# SCH___2022-11-10.net
KiCad netlist of a schematic drawn in EasyEDA
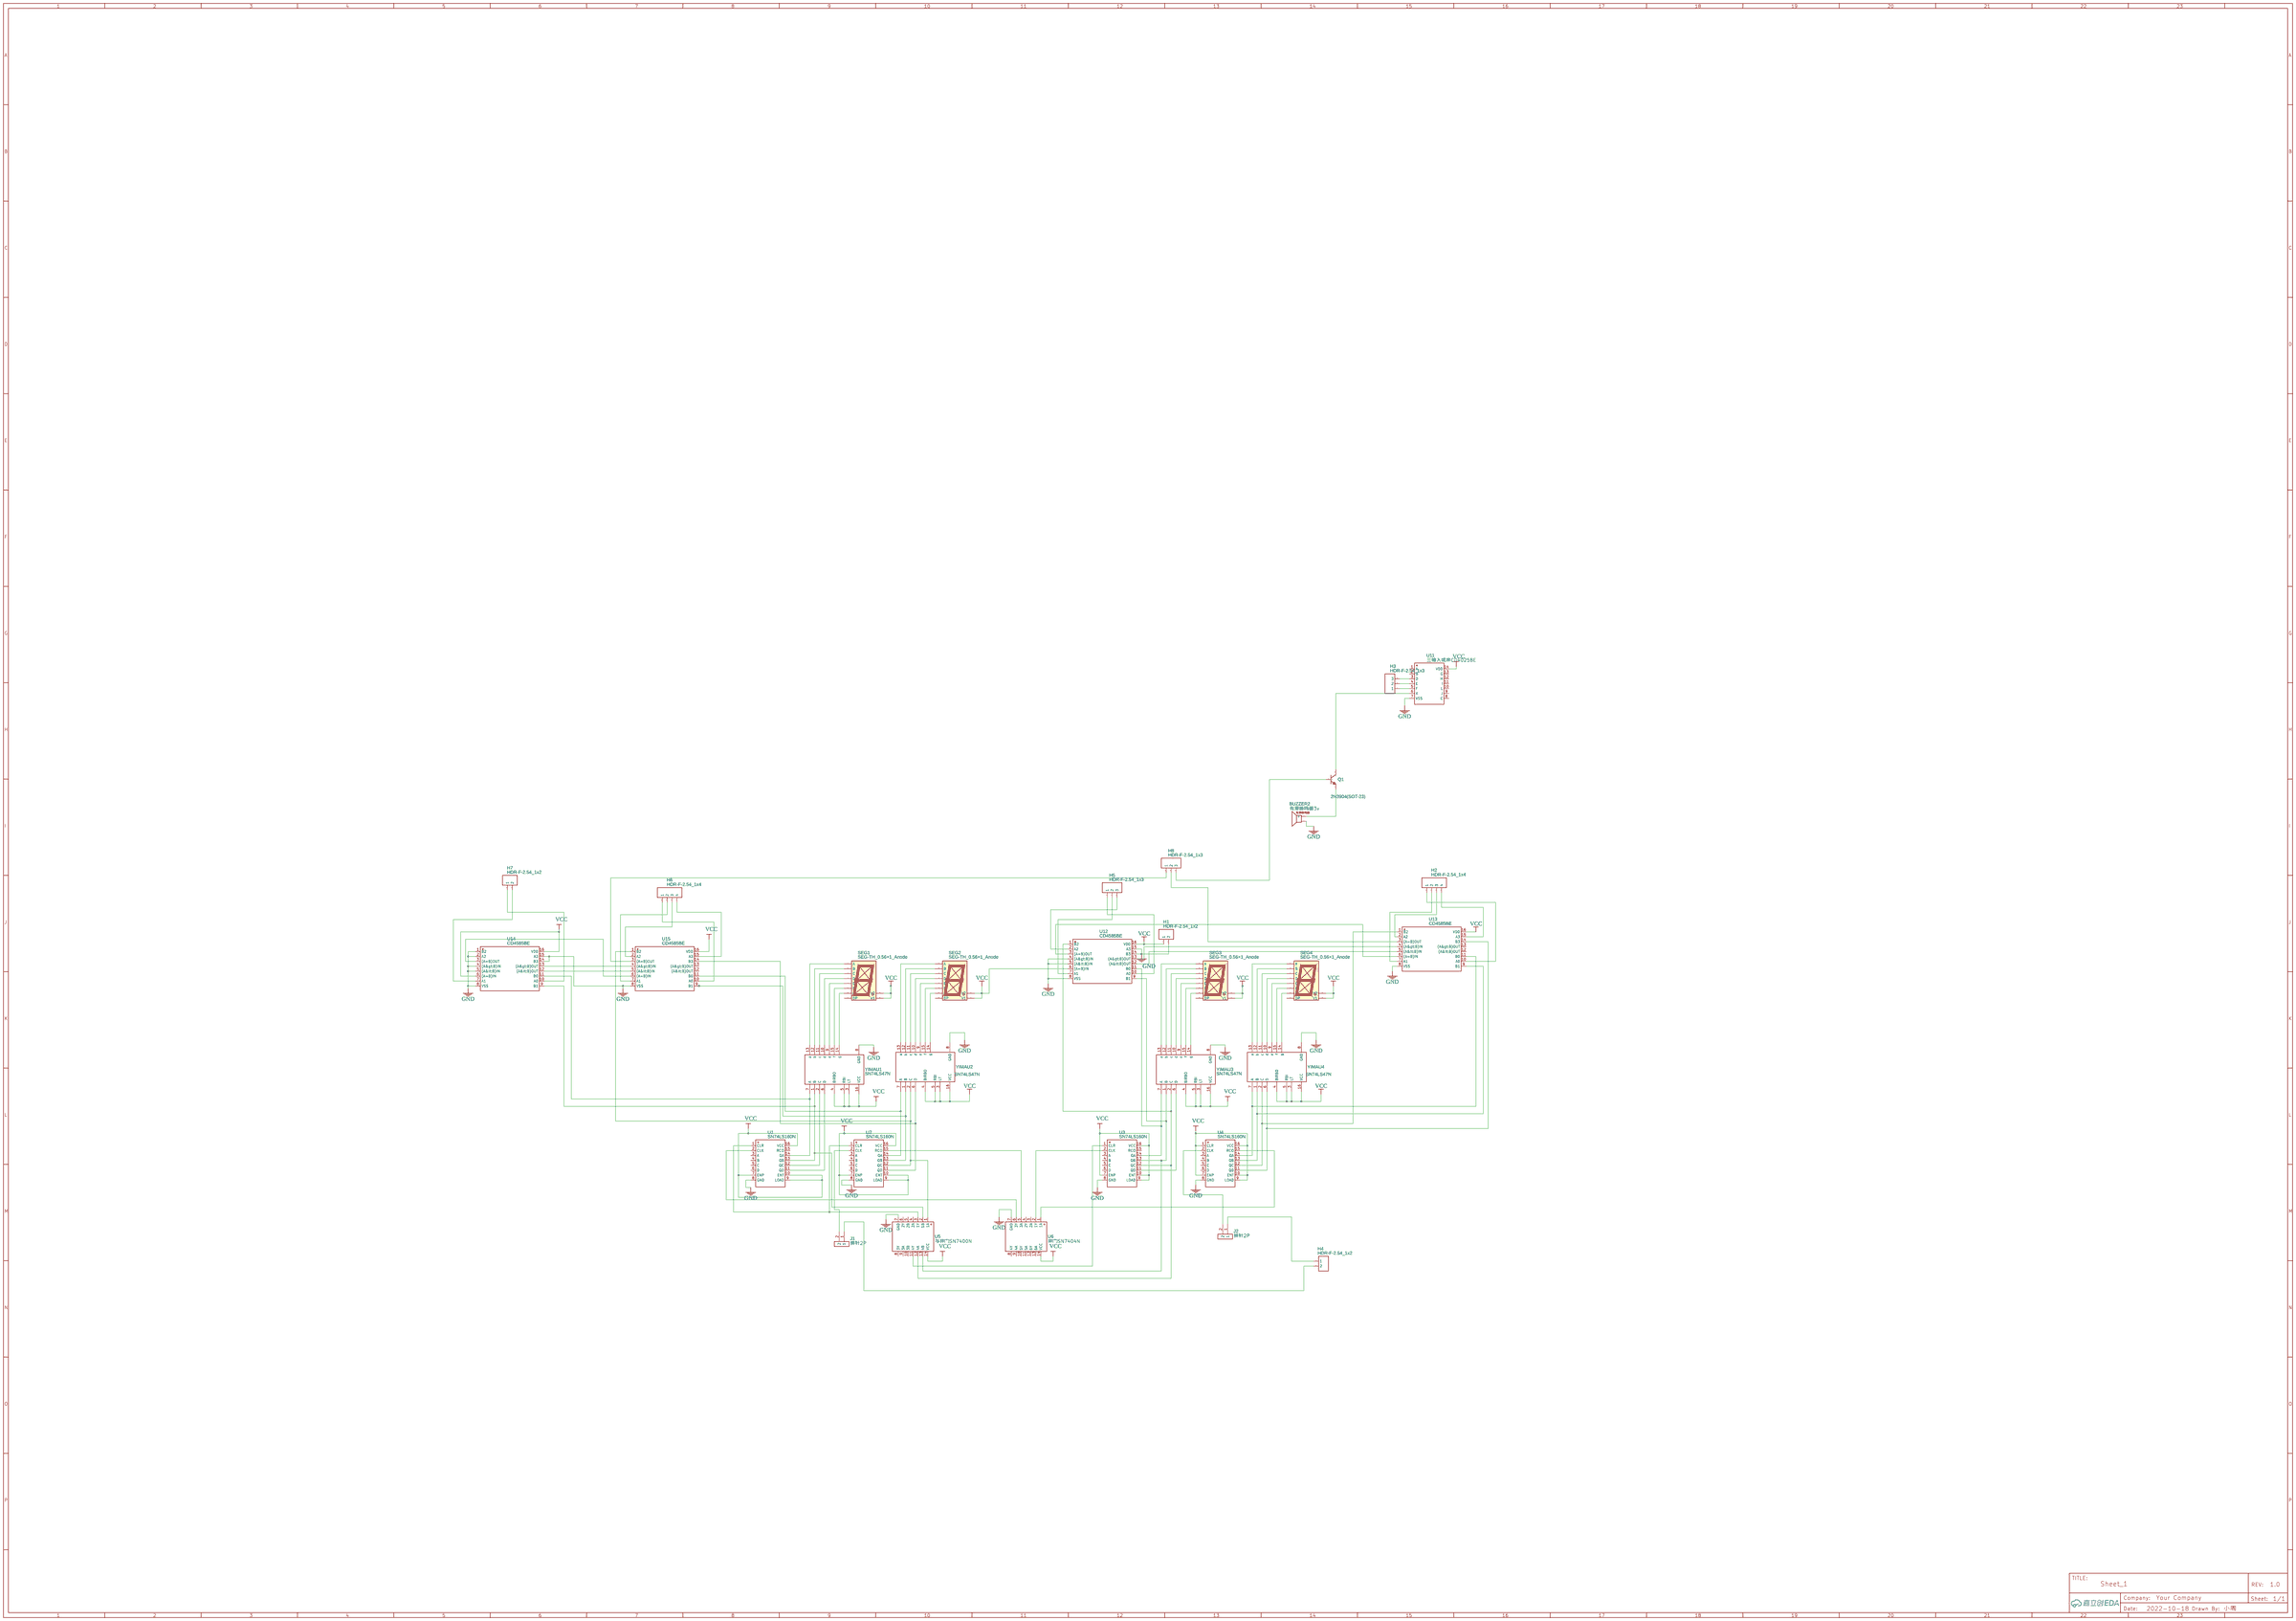
[diagram p0: schematic sheet]

(export (version "E")
  (design (tool "Eeschema 10.0.6"))
  (components
    (comp (ref "BUZZER2")
      (value "有源蜂鸣器3v")
      (fields (field (name "BOM_Manufacturer Part") "TMB12A12") (field (name "BOM_Supplier Part") "C96079"))
      (libsource (lib "") (part "有源蜂鸣器3v"))
    )
    (comp (ref "H1")
      (value "HDR-F-2.54_1x2")
      (fields (field (name "BOM_Supplier Part") "C49661"))
      (libsource (lib "") (part "HDR-F-2.54_1x2_1"))
    )
    (comp (ref "H2")
      (value "HDR-F-2.54_1x4")
      (fields (field (name "BOM_Supplier Part") "C225501"))
      (libsource (lib "") (part "HDR-F-2.54_1x4"))
    )
    (comp (ref "H3")
      (value "HDR-F-2.54_1x3")
      (fields (field (name "BOM_Supplier Part") "C146690"))
      (libsource (lib "") (part "HDR-F-2.54_1x3_1"))
    )
    (comp (ref "H4")
      (value "HDR-F-2.54_1x2")
      (fields (field (name "BOM_Supplier Part") "C49661"))
      (libsource (lib "") (part "HDR-F-2.54_1x2"))
    )
    (comp (ref "H5")
      (value "HDR-F-2.54_1x3")
      (fields (field (name "BOM_Supplier Part") "C146690"))
      (libsource (lib "") (part "HDR-F-2.54_1x3"))
    )
    (comp (ref "H6")
      (value "HDR-F-2.54_1x4")
      (fields (field (name "BOM_Supplier Part") "C225501"))
      (libsource (lib "") (part "HDR-F-2.54_1x4"))
    )
    (comp (ref "H7")
      (value "HDR-F-2.54_1x2")
      (fields (field (name "BOM_Supplier Part") "C49661"))
      (libsource (lib "") (part "HDR-F-2.54_1x2_1"))
    )
    (comp (ref "H8")
      (value "HDR-F-2.54_1x3")
      (fields (field (name "BOM_Supplier Part") "C146690"))
      (libsource (lib "") (part "HDR-F-2.54_1x3"))
    )
    (comp (ref "J1") (value "排针2P") (libsource (lib "") (part "排针2P")))
    (comp (ref "J2") (value "排针2P") (libsource (lib "") (part "排针2P")))
    (comp (ref "Q1")
      (value "2N3904(SOT-23)")
      (fields
        (field (name "BOM_Manufacturer Part") "2n3904S-RTK/PS")
        (field (name "BOM_Supplier Part") "C18536")
      )
      (libsource (lib "") (part "2N3904(SOT-23)"))
    )
    (comp (ref "SEG1")
      (value "SEG-TH_0.56×1_Anode")
      (fields (field (name "BOM_Supplier Part") "C8092"))
      (libsource (lib "") (part "SEG-TH_0.56×1_Anode"))
    )
    (comp (ref "SEG2")
      (value "SEG-TH_0.56×1_Anode")
      (fields (field (name "BOM_Supplier Part") "C8092"))
      (libsource (lib "") (part "SEG-TH_0.56×1_Anode"))
    )
    (comp (ref "SEG3")
      (value "SEG-TH_0.56×1_Anode")
      (fields (field (name "BOM_Supplier Part") "C8092"))
      (libsource (lib "") (part "SEG-TH_0.56×1_Anode"))
    )
    (comp (ref "SEG4")
      (value "SEG-TH_0.56×1_Anode")
      (fields (field (name "BOM_Supplier Part") "C8092"))
      (libsource (lib "") (part "SEG-TH_0.56×1_Anode"))
    )
    (comp (ref "U1")
      (value "SN74LS160N")
      (fields
        (field (name "BOM_Manufacturer Part") "CC0805JRNPO9BN821")
        (field (name "BOM_Supplier Part") "C113834")
      )
      (libsource (lib "") (part "SN74LS160N"))
    )
    (comp (ref "U2")
      (value "SN74LS160N")
      (fields
        (field (name "BOM_Manufacturer Part") "CC0805JRNPO9BN821")
        (field (name "BOM_Supplier Part") "C113834")
      )
      (libsource (lib "") (part "SN74LS160N"))
    )
    (comp (ref "U3")
      (value "SN74LS160N")
      (fields
        (field (name "BOM_Manufacturer Part") "CC0805JRNPO9BN821")
        (field (name "BOM_Supplier Part") "C113834")
      )
      (libsource (lib "") (part "SN74LS160N"))
    )
    (comp (ref "U4")
      (value "SN74LS160N")
      (fields
        (field (name "BOM_Manufacturer Part") "CC0805JRNPO9BN821")
        (field (name "BOM_Supplier Part") "C113834")
      )
      (libsource (lib "") (part "SN74LS160N"))
    )
    (comp (ref "U5") (value "与非门SN7400N") (libsource (lib "") (part "SN7400N")))
    (comp (ref "U6") (value "非门SN7404N") (libsource (lib "") (part "SN7404N")))
    (comp (ref "U11")
      (value "三输入或非CD4025BE")
      (fields (field (name "BOM_Manufacturer Part") "CD4025BE") (field (name "BOM_Supplier Part") "C28214"))
      (libsource (lib "") (part "CD4025BE"))
    )
    (comp (ref "U12")
      (value "CD4585BE")
      (fields (field (name "BOM_Supplier Part") "C31466"))
      (libsource (lib "") (part "CD4585BE"))
    )
    (comp (ref "U13")
      (value "CD4585BE")
      (fields (field (name "BOM_Supplier Part") "C31466"))
      (libsource (lib "") (part "CD4585BE"))
    )
    (comp (ref "U14")
      (value "CD4585BE")
      (fields (field (name "BOM_Supplier Part") "C31466"))
      (libsource (lib "") (part "CD4585BE"))
    )
    (comp (ref "U15")
      (value "CD4585BE")
      (fields (field (name "BOM_Supplier Part") "C31466"))
      (libsource (lib "") (part "CD4585BE"))
    )
    (comp (ref "YIMAU1")
      (value "SN74LS47N")
      (fields (field (name "BOM_Supplier Part") "C129379"))
      (libsource (lib "") (part "Unknown_1690_-1115"))
    )
    (comp (ref "YIMAU2")
      (value "SN74LS47N")
      (fields (field (name "BOM_Supplier Part") "C129379"))
      (libsource (lib "") (part "Unknown_1875_-1120"))
    )
    (comp (ref "YIMAU3")
      (value "SN74LS47N")
      (fields (field (name "BOM_Supplier Part") "C129379"))
      (libsource (lib "") (part "Unknown_2405_-1115"))
    )
    (comp (ref "YIMAU4")
      (value "SN74LS47N")
      (fields (field (name "BOM_Supplier Part") "C129379"))
      (libsource (lib "") (part "Unknown_2590_-1120"))
    )
  )
  (nets
    (net (code "1") (name "GND") (class "Default")
      (node (ref "BUZZER2") (pin "-") (pinfunction "-_-") (pintype "unspecified"))
      (node (ref "H1") (pin "2") (pinfunction "2_2") (pintype "input"))
      (node (ref "U1") (pin "8") (pinfunction "GND_8") (pintype "unspecified"))
      (node (ref "U11") (pin "7") (pinfunction "VSS_7") (pintype "unspecified"))
      (node (ref "U12") (pin "14") (pinfunction "B3_14") (pintype "unspecified"))
      (node (ref "U12") (pin "15") (pinfunction "A3_15") (pintype "unspecified"))
      (node (ref "U12") (pin "4") (pinfunction "(A&gt;B)IN_4") (pintype "unspecified"))
      (node (ref "U12") (pin "5") (pinfunction "(A&lt;B)IN_5") (pintype "unspecified"))
      (node (ref "U12") (pin "8") (pinfunction "VSS_8") (pintype "unspecified"))
      (node (ref "U13") (pin "8") (pinfunction "VSS_8") (pintype "unspecified"))
      (node (ref "U14") (pin "1") (pinfunction "B2_1") (pintype "unspecified"))
      (node (ref "U14") (pin "14") (pinfunction "B3_14") (pintype "unspecified"))
      (node (ref "U14") (pin "15") (pinfunction "A3_15") (pintype "unspecified"))
      (node (ref "U14") (pin "2") (pinfunction "A2_2") (pintype "unspecified"))
      (node (ref "U14") (pin "4") (pinfunction "(A&gt;B)IN_4") (pintype "unspecified"))
      (node (ref "U14") (pin "5") (pinfunction "(A&lt;B)IN_5") (pintype "unspecified"))
      (node (ref "U14") (pin "8") (pinfunction "VSS_8") (pintype "unspecified"))
      (node (ref "U15") (pin "8") (pinfunction "VSS_8") (pintype "unspecified"))
      (node (ref "U2") (pin "8") (pinfunction "GND_8") (pintype "unspecified"))
      (node (ref "U3") (pin "8") (pinfunction "GND_8") (pintype "unspecified"))
      (node (ref "U4") (pin "8") (pinfunction "GND_8") (pintype "unspecified"))
      (node (ref "U5") (pin "7") (pinfunction "GND_7") (pintype "unspecified"))
      (node (ref "U6") (pin "7") (pinfunction "GND_7") (pintype "unspecified"))
      (node (ref "YIMAU1") (pin "8") (pinfunction "GND_8") (pintype "passive"))
      (node (ref "YIMAU2") (pin "8") (pinfunction "GND_8") (pintype "passive"))
      (node (ref "YIMAU3") (pin "8") (pinfunction "GND_8") (pintype "passive"))
      (node (ref "YIMAU4") (pin "8") (pinfunction "GND_8") (pintype "passive"))
    )
    (net (code "2") (name "Net-(H4-Pad1)") (class "Default")
      (node (ref "H4") (pin "1") (pinfunction "1_1") (pintype "input"))
      (node (ref "J2") (pin "1") (pinfunction "1_1") (pintype "unspecified"))
    )
    (net (code "3") (name "Net-(H4-Pad2)") (class "Default")
      (node (ref "H4") (pin "2") (pinfunction "2_2") (pintype "input"))
      (node (ref "J1") (pin "1") (pinfunction "1_1") (pintype "unspecified"))
    )
    (net (code "4") (name "Net-(Q1-B)") (class "Default")
      (node (ref "H8") (pin "3") (pinfunction "3_3") (pintype "input"))
      (node (ref "Q1") (pin "2") (pinfunction "B_2") (pintype "input"))
    )
    (net (code "5") (name "Net-(Q1-C)") (class "Default")
      (node (ref "Q1") (pin "3") (pinfunction "C_3") (pintype "input"))
      (node (ref "U11") (pin "6") (pinfunction "K_6") (pintype "unspecified"))
    )
    (net (code "6") (name "Net-(Q1-E)") (class "Default")
      (node (ref "BUZZER2") (pin "+") (pinfunction "+_+") (pintype "unspecified"))
      (node (ref "Q1") (pin "1") (pinfunction "E_1") (pintype "input"))
    )
    (net (code "7") (name "Net-(SEG1-A)") (class "Default")
      (node (ref "SEG1") (pin "7") (pinfunction "A_7") (pintype "unspecified"))
      (node (ref "YIMAU1") (pin "13") (pinfunction "a_13") (pintype "unspecified"))
    )
    (net (code "8") (name "Net-(SEG1-B)") (class "Default")
      (node (ref "SEG1") (pin "6") (pinfunction "B_6") (pintype "unspecified"))
      (node (ref "YIMAU1") (pin "12") (pinfunction "b_12") (pintype "unspecified"))
    )
    (net (code "9") (name "Net-(SEG1-C)") (class "Default")
      (node (ref "SEG1") (pin "4") (pinfunction "C_4") (pintype "unspecified"))
      (node (ref "YIMAU1") (pin "11") (pinfunction "c_11") (pintype "unspecified"))
    )
    (net (code "10") (name "Net-(SEG1-D)") (class "Default")
      (node (ref "SEG1") (pin "2") (pinfunction "D_2") (pintype "unspecified"))
      (node (ref "YIMAU1") (pin "10") (pinfunction "d_10") (pintype "unspecified"))
    )
    (net (code "11") (name "Net-(SEG1-E)") (class "Default")
      (node (ref "SEG1") (pin "1") (pinfunction "E_1") (pintype "unspecified"))
      (node (ref "YIMAU1") (pin "9") (pinfunction "e_9") (pintype "unspecified"))
    )
    (net (code "12") (name "Net-(SEG1-F)") (class "Default")
      (node (ref "SEG1") (pin "9") (pinfunction "F_9") (pintype "unspecified"))
      (node (ref "YIMAU1") (pin "15") (pinfunction "f_15") (pintype "unspecified"))
    )
    (net (code "13") (name "Net-(SEG1-G)") (class "Default")
      (node (ref "SEG1") (pin "10") (pinfunction "G_10") (pintype "unspecified"))
      (node (ref "YIMAU1") (pin "14") (pinfunction "g_14") (pintype "unspecified"))
    )
    (net (code "14") (name "Net-(SEG2-A)") (class "Default")
      (node (ref "SEG2") (pin "7") (pinfunction "A_7") (pintype "unspecified"))
      (node (ref "YIMAU2") (pin "13") (pinfunction "a_13") (pintype "unspecified"))
    )
    (net (code "15") (name "Net-(SEG2-B)") (class "Default")
      (node (ref "SEG2") (pin "6") (pinfunction "B_6") (pintype "unspecified"))
      (node (ref "YIMAU2") (pin "12") (pinfunction "b_12") (pintype "unspecified"))
    )
    (net (code "16") (name "Net-(SEG2-C)") (class "Default")
      (node (ref "SEG2") (pin "4") (pinfunction "C_4") (pintype "unspecified"))
      (node (ref "YIMAU2") (pin "11") (pinfunction "c_11") (pintype "unspecified"))
    )
    (net (code "17") (name "Net-(SEG2-D)") (class "Default")
      (node (ref "SEG2") (pin "2") (pinfunction "D_2") (pintype "unspecified"))
      (node (ref "YIMAU2") (pin "10") (pinfunction "d_10") (pintype "unspecified"))
    )
    (net (code "18") (name "Net-(SEG2-E)") (class "Default")
      (node (ref "SEG2") (pin "1") (pinfunction "E_1") (pintype "unspecified"))
      (node (ref "YIMAU2") (pin "9") (pinfunction "e_9") (pintype "unspecified"))
    )
    (net (code "19") (name "Net-(SEG2-F)") (class "Default")
      (node (ref "SEG2") (pin "9") (pinfunction "F_9") (pintype "unspecified"))
      (node (ref "YIMAU2") (pin "15") (pinfunction "f_15") (pintype "unspecified"))
    )
    (net (code "20") (name "Net-(SEG2-G)") (class "Default")
      (node (ref "SEG2") (pin "10") (pinfunction "G_10") (pintype "unspecified"))
      (node (ref "YIMAU2") (pin "14") (pinfunction "g_14") (pintype "unspecified"))
    )
    (net (code "21") (name "Net-(SEG3-A)") (class "Default")
      (node (ref "SEG3") (pin "7") (pinfunction "A_7") (pintype "unspecified"))
      (node (ref "YIMAU3") (pin "13") (pinfunction "a_13") (pintype "unspecified"))
    )
    (net (code "22") (name "Net-(SEG3-B)") (class "Default")
      (node (ref "SEG3") (pin "6") (pinfunction "B_6") (pintype "unspecified"))
      (node (ref "YIMAU3") (pin "12") (pinfunction "b_12") (pintype "unspecified"))
    )
    (net (code "23") (name "Net-(SEG3-C)") (class "Default")
      (node (ref "SEG3") (pin "4") (pinfunction "C_4") (pintype "unspecified"))
      (node (ref "YIMAU3") (pin "11") (pinfunction "c_11") (pintype "unspecified"))
    )
    (net (code "24") (name "Net-(SEG3-D)") (class "Default")
      (node (ref "SEG3") (pin "2") (pinfunction "D_2") (pintype "unspecified"))
      (node (ref "YIMAU3") (pin "10") (pinfunction "d_10") (pintype "unspecified"))
    )
    (net (code "25") (name "Net-(SEG3-E)") (class "Default")
      (node (ref "SEG3") (pin "1") (pinfunction "E_1") (pintype "unspecified"))
      (node (ref "YIMAU3") (pin "9") (pinfunction "e_9") (pintype "unspecified"))
    )
    (net (code "26") (name "Net-(SEG3-F)") (class "Default")
      (node (ref "SEG3") (pin "9") (pinfunction "F_9") (pintype "unspecified"))
      (node (ref "YIMAU3") (pin "15") (pinfunction "f_15") (pintype "unspecified"))
    )
    (net (code "27") (name "Net-(SEG3-G)") (class "Default")
      (node (ref "SEG3") (pin "10") (pinfunction "G_10") (pintype "unspecified"))
      (node (ref "YIMAU3") (pin "14") (pinfunction "g_14") (pintype "unspecified"))
    )
    (net (code "28") (name "Net-(SEG4-A)") (class "Default")
      (node (ref "SEG4") (pin "7") (pinfunction "A_7") (pintype "unspecified"))
      (node (ref "YIMAU4") (pin "13") (pinfunction "a_13") (pintype "unspecified"))
    )
    (net (code "29") (name "Net-(SEG4-B)") (class "Default")
      (node (ref "SEG4") (pin "6") (pinfunction "B_6") (pintype "unspecified"))
      (node (ref "YIMAU4") (pin "12") (pinfunction "b_12") (pintype "unspecified"))
    )
    (net (code "30") (name "Net-(SEG4-C)") (class "Default")
      (node (ref "SEG4") (pin "4") (pinfunction "C_4") (pintype "unspecified"))
      (node (ref "YIMAU4") (pin "11") (pinfunction "c_11") (pintype "unspecified"))
    )
    (net (code "31") (name "Net-(SEG4-D)") (class "Default")
      (node (ref "SEG4") (pin "2") (pinfunction "D_2") (pintype "unspecified"))
      (node (ref "YIMAU4") (pin "10") (pinfunction "d_10") (pintype "unspecified"))
    )
    (net (code "32") (name "Net-(SEG4-E)") (class "Default")
      (node (ref "SEG4") (pin "1") (pinfunction "E_1") (pintype "unspecified"))
      (node (ref "YIMAU4") (pin "9") (pinfunction "e_9") (pintype "unspecified"))
    )
    (net (code "33") (name "Net-(SEG4-F)") (class "Default")
      (node (ref "SEG4") (pin "9") (pinfunction "F_9") (pintype "unspecified"))
      (node (ref "YIMAU4") (pin "15") (pinfunction "f_15") (pintype "unspecified"))
    )
    (net (code "34") (name "Net-(SEG4-G)") (class "Default")
      (node (ref "SEG4") (pin "10") (pinfunction "G_10") (pintype "unspecified"))
      (node (ref "YIMAU4") (pin "14") (pinfunction "g_14") (pintype "unspecified"))
    )
    (net (code "35") (name "Net-(U1-CLK)") (class "Default")
      (node (ref "U1") (pin "2") (pinfunction "CLK_2") (pintype "unspecified"))
      (node (ref "U6") (pin "6") (pinfunction "3Y_6") (pintype "unspecified"))
    )
    (net (code "36") (name "Net-(U1-CLR)") (class "Default")
      (node (ref "U1") (pin "1") (pinfunction "CLR_1") (pintype "unspecified"))
      (node (ref "U2") (pin "1") (pinfunction "CLR_1") (pintype "unspecified"))
      (node (ref "U5") (pin "3") (pinfunction "1Y_3") (pintype "unspecified"))
    )
    (net (code "37") (name "Net-(U1-QA)") (class "Default")
      (node (ref "U1") (pin "14") (pinfunction "QA_14") (pintype "unspecified"))
      (node (ref "U14") (pin "11") (pinfunction "B0_11") (pintype "unspecified"))
      (node (ref "YIMAU1") (pin "7") (pinfunction "A_7") (pintype "unspecified"))
    )
    (net (code "38") (name "Net-(U1-QB)") (class "Default")
      (node (ref "U1") (pin "13") (pinfunction "QB_13") (pintype "unspecified"))
      (node (ref "U14") (pin "9") (pinfunction "B1_9") (pintype "unspecified"))
      (node (ref "U5") (pin "2") (pinfunction "1B_2") (pintype "unspecified"))
      (node (ref "YIMAU1") (pin "1") (pinfunction "B_1") (pintype "unspecified"))
    )
    (net (code "39") (name "Net-(U1-QC)") (class "Default")
      (node (ref "U1") (pin "12") (pinfunction "QC_12") (pintype "unspecified"))
      (node (ref "YIMAU1") (pin "2") (pinfunction "C_2") (pintype "unspecified"))
    )
    (net (code "40") (name "Net-(U1-QD)") (class "Default")
      (node (ref "U1") (pin "11") (pinfunction "QD_11") (pintype "unspecified"))
      (node (ref "YIMAU1") (pin "6") (pinfunction "D_6") (pintype "unspecified"))
    )
    (net (code "41") (name "Net-(U2-CLK)") (class "Default")
      (node (ref "J1") (pin "2") (pinfunction "2_2") (pintype "unspecified"))
      (node (ref "U2") (pin "2") (pinfunction "CLK_2") (pintype "unspecified"))
    )
    (net (code "42") (name "Net-(U2-RCO)") (class "Default")
      (node (ref "U2") (pin "15") (pinfunction "RCO_15") (pintype "unspecified"))
      (node (ref "U6") (pin "5") (pinfunction "3A_5") (pintype "unspecified"))
    )
    (net (code "43") (name "Net-(U3-CLK)") (class "Default")
      (node (ref "U3") (pin "2") (pinfunction "CLK_2") (pintype "unspecified"))
      (node (ref "U6") (pin "2") (pinfunction "1Y_2") (pintype "unspecified"))
    )
    (net (code "44") (name "Net-(U3-CLR)") (class "Default")
      (node (ref "U3") (pin "1") (pinfunction "CLR_1") (pintype "unspecified"))
      (node (ref "U5") (pin "11") (pinfunction "4Y_11") (pintype "unspecified"))
    )
    (net (code "45") (name "Net-(U3-QD)") (class "Default")
      (node (ref "U3") (pin "11") (pinfunction "QD_11") (pintype "unspecified"))
      (node (ref "YIMAU3") (pin "6") (pinfunction "D_6") (pintype "unspecified"))
    )
    (net (code "46") (name "Net-(U4-CLK)") (class "Default")
      (node (ref "J2") (pin "2") (pinfunction "2_2") (pintype "unspecified"))
      (node (ref "U4") (pin "2") (pinfunction "CLK_2") (pintype "unspecified"))
    )
    (net (code "47") (name "Net-(U4-RCO)") (class "Default")
      (node (ref "U4") (pin "15") (pinfunction "RCO_15") (pintype "unspecified"))
      (node (ref "U6") (pin "1") (pinfunction "1A_1") (pintype "unspecified"))
    )
    (net (code "48") (name "Net-(U11-D)") (class "Default")
      (node (ref "H3") (pin "3") (pinfunction "3_3") (pintype "input"))
      (node (ref "U11") (pin "3") (pinfunction "D_3") (pintype "unspecified"))
    )
    (net (code "49") (name "Net-(U11-E)") (class "Default")
      (node (ref "H3") (pin "2") (pinfunction "2_2") (pintype "input"))
      (node (ref "U11") (pin "4") (pinfunction "E_4") (pintype "unspecified"))
    )
    (net (code "50") (name "Net-(U11-F)") (class "Default")
      (node (ref "H3") (pin "1") (pinfunction "1_1") (pintype "input"))
      (node (ref "U11") (pin "5") (pinfunction "F_5") (pintype "unspecified"))
    )
    (net (code "51") (name "Net-(U12-(A&gt;B)OUT)") (class "Default")
      (node (ref "U12") (pin "13") (pinfunction "(A&gt;B)OUT_13") (pintype "unspecified"))
      (node (ref "U13") (pin "4") (pinfunction "(A&gt;B)IN_4") (pintype "unspecified"))
    )
    (net (code "52") (name "Net-(U12-(A&lt;B)OUT)") (class "Default")
      (node (ref "U12") (pin "12") (pinfunction "(A&lt;B)OUT_12") (pintype "unspecified"))
      (node (ref "U13") (pin "5") (pinfunction "(A&lt;B)IN_5") (pintype "unspecified"))
    )
    (net (code "53") (name "Net-(U12-(A=B)OUT)") (class "Default")
      (node (ref "U12") (pin "3") (pinfunction "(A=B)OUT_3") (pintype "unspecified"))
      (node (ref "U13") (pin "6") (pinfunction "(A=B)IN_6") (pintype "unspecified"))
    )
    (net (code "54") (name "Net-(U12-A0)") (class "Default")
      (node (ref "H5") (pin "1") (pinfunction "1_1") (pintype "input"))
      (node (ref "U12") (pin "10") (pinfunction "A0_10") (pintype "unspecified"))
    )
    (net (code "55") (name "Net-(U12-A1)") (class "Default")
      (node (ref "H5") (pin "2") (pinfunction "2_2") (pintype "input"))
      (node (ref "U12") (pin "7") (pinfunction "A1_7") (pintype "unspecified"))
    )
    (net (code "56") (name "Net-(U12-A2)") (class "Default")
      (node (ref "H5") (pin "3") (pinfunction "3_3") (pintype "input"))
      (node (ref "U12") (pin "2") (pinfunction "A2_2") (pintype "unspecified"))
    )
    (net (code "57") (name "Net-(U12-B0)") (class "Default")
      (node (ref "U12") (pin "11") (pinfunction "B0_11") (pintype "unspecified"))
      (node (ref "U3") (pin "14") (pinfunction "QA_14") (pintype "unspecified"))
      (node (ref "YIMAU3") (pin "7") (pinfunction "A_7") (pintype "unspecified"))
    )
    (net (code "58") (name "Net-(U12-B1)") (class "Default")
      (node (ref "U12") (pin "9") (pinfunction "B1_9") (pintype "unspecified"))
      (node (ref "U3") (pin "13") (pinfunction "QB_13") (pintype "unspecified"))
      (node (ref "U5") (pin "13") (pinfunction "4B_13") (pintype "unspecified"))
      (node (ref "YIMAU3") (pin "1") (pinfunction "B_1") (pintype "unspecified"))
    )
    (net (code "59") (name "Net-(U12-B2)") (class "Default")
      (node (ref "U12") (pin "1") (pinfunction "B2_1") (pintype "unspecified"))
      (node (ref "U3") (pin "12") (pinfunction "QC_12") (pintype "unspecified"))
      (node (ref "U5") (pin "12") (pinfunction "4A_12") (pintype "unspecified"))
      (node (ref "YIMAU3") (pin "2") (pinfunction "C_2") (pintype "unspecified"))
    )
    (net (code "60") (name "Net-(U13-(A=B)OUT)") (class "Default")
      (node (ref "H8") (pin "2") (pinfunction "2_2") (pintype "input"))
      (node (ref "U13") (pin "3") (pinfunction "(A=B)OUT_3") (pintype "unspecified"))
    )
    (net (code "61") (name "Net-(U13-A0)") (class "Default")
      (node (ref "H2") (pin "1") (pinfunction "1_1") (pintype "unspecified"))
      (node (ref "U13") (pin "10") (pinfunction "A0_10") (pintype "unspecified"))
    )
    (net (code "62") (name "Net-(U13-A1)") (class "Default")
      (node (ref "H2") (pin "2") (pinfunction "2_2") (pintype "unspecified"))
      (node (ref "U13") (pin "7") (pinfunction "A1_7") (pintype "unspecified"))
    )
    (net (code "63") (name "Net-(U13-A2)") (class "Default")
      (node (ref "H2") (pin "3") (pinfunction "3_3") (pintype "unspecified"))
      (node (ref "U13") (pin "2") (pinfunction "A2_2") (pintype "unspecified"))
    )
    (net (code "64") (name "Net-(U13-A3)") (class "Default")
      (node (ref "H2") (pin "4") (pinfunction "4_4") (pintype "unspecified"))
      (node (ref "U13") (pin "15") (pinfunction "A3_15") (pintype "unspecified"))
    )
    (net (code "65") (name "Net-(U13-B0)") (class "Default")
      (node (ref "U13") (pin "11") (pinfunction "B0_11") (pintype "unspecified"))
      (node (ref "U4") (pin "14") (pinfunction "QA_14") (pintype "unspecified"))
      (node (ref "YIMAU4") (pin "7") (pinfunction "A_7") (pintype "unspecified"))
    )
    (net (code "66") (name "Net-(U13-B1)") (class "Default")
      (node (ref "U13") (pin "9") (pinfunction "B1_9") (pintype "unspecified"))
      (node (ref "U4") (pin "13") (pinfunction "QB_13") (pintype "unspecified"))
      (node (ref "YIMAU4") (pin "1") (pinfunction "B_1") (pintype "unspecified"))
    )
    (net (code "67") (name "Net-(U13-B2)") (class "Default")
      (node (ref "U13") (pin "1") (pinfunction "B2_1") (pintype "unspecified"))
      (node (ref "U4") (pin "12") (pinfunction "QC_12") (pintype "unspecified"))
      (node (ref "YIMAU4") (pin "2") (pinfunction "C_2") (pintype "unspecified"))
    )
    (net (code "68") (name "Net-(U13-B3)") (class "Default")
      (node (ref "U13") (pin "14") (pinfunction "B3_14") (pintype "unspecified"))
      (node (ref "U4") (pin "11") (pinfunction "QD_11") (pintype "unspecified"))
      (node (ref "YIMAU4") (pin "6") (pinfunction "D_6") (pintype "unspecified"))
    )
    (net (code "69") (name "Net-(U14-(A&gt;B)OUT)") (class "Default")
      (node (ref "U14") (pin "13") (pinfunction "(A&gt;B)OUT_13") (pintype "unspecified"))
      (node (ref "U15") (pin "4") (pinfunction "(A&gt;B)IN_4") (pintype "unspecified"))
    )
    (net (code "70") (name "Net-(U14-(A&lt;B)OUT)") (class "Default")
      (node (ref "U14") (pin "12") (pinfunction "(A&lt;B)OUT_12") (pintype "unspecified"))
      (node (ref "U15") (pin "5") (pinfunction "(A&lt;B)IN_5") (pintype "unspecified"))
    )
    (net (code "71") (name "Net-(U14-(A=B)OUT)") (class "Default")
      (node (ref "U14") (pin "3") (pinfunction "(A=B)OUT_3") (pintype "unspecified"))
      (node (ref "U15") (pin "6") (pinfunction "(A=B)IN_6") (pintype "unspecified"))
    )
    (net (code "72") (name "Net-(U14-A0)") (class "Default")
      (node (ref "H7") (pin "1") (pinfunction "1_1") (pintype "input"))
      (node (ref "U14") (pin "10") (pinfunction "A0_10") (pintype "unspecified"))
    )
    (net (code "73") (name "Net-(U14-A1)") (class "Default")
      (node (ref "H7") (pin "2") (pinfunction "2_2") (pintype "input"))
      (node (ref "U14") (pin "7") (pinfunction "A1_7") (pintype "unspecified"))
    )
    (net (code "74") (name "Net-(U15-(A=B)OUT)") (class "Default")
      (node (ref "H8") (pin "1") (pinfunction "1_1") (pintype "input"))
      (node (ref "U15") (pin "3") (pinfunction "(A=B)OUT_3") (pintype "unspecified"))
    )
    (net (code "75") (name "Net-(U15-A0)") (class "Default")
      (node (ref "H6") (pin "1") (pinfunction "1_1") (pintype "unspecified"))
      (node (ref "U15") (pin "10") (pinfunction "A0_10") (pintype "unspecified"))
    )
    (net (code "76") (name "Net-(U15-A1)") (class "Default")
      (node (ref "H6") (pin "2") (pinfunction "2_2") (pintype "unspecified"))
      (node (ref "U15") (pin "7") (pinfunction "A1_7") (pintype "unspecified"))
    )
    (net (code "77") (name "Net-(U15-A2)") (class "Default")
      (node (ref "H6") (pin "3") (pinfunction "3_3") (pintype "unspecified"))
      (node (ref "U15") (pin "2") (pinfunction "A2_2") (pintype "unspecified"))
    )
    (net (code "78") (name "Net-(U15-A3)") (class "Default")
      (node (ref "H6") (pin "4") (pinfunction "4_4") (pintype "unspecified"))
      (node (ref "U15") (pin "15") (pinfunction "A3_15") (pintype "unspecified"))
    )
    (net (code "79") (name "Net-(U15-B0)") (class "Default")
      (node (ref "U15") (pin "11") (pinfunction "B0_11") (pintype "unspecified"))
      (node (ref "U2") (pin "14") (pinfunction "QA_14") (pintype "unspecified"))
      (node (ref "YIMAU2") (pin "7") (pinfunction "A_7") (pintype "unspecified"))
    )
    (net (code "80") (name "Net-(U15-B1)") (class "Default")
      (node (ref "U15") (pin "9") (pinfunction "B1_9") (pintype "unspecified"))
      (node (ref "U2") (pin "13") (pinfunction "QB_13") (pintype "unspecified"))
      (node (ref "YIMAU2") (pin "1") (pinfunction "B_1") (pintype "unspecified"))
    )
    (net (code "81") (name "Net-(U15-B2)") (class "Default")
      (node (ref "U15") (pin "1") (pinfunction "B2_1") (pintype "unspecified"))
      (node (ref "U2") (pin "12") (pinfunction "QC_12") (pintype "unspecified"))
      (node (ref "U5") (pin "1") (pinfunction "1A_1") (pintype "unspecified"))
      (node (ref "YIMAU2") (pin "2") (pinfunction "C_2") (pintype "unspecified"))
    )
    (net (code "82") (name "Net-(U15-B3)") (class "Default")
      (node (ref "U15") (pin "14") (pinfunction "B3_14") (pintype "unspecified"))
      (node (ref "U2") (pin "11") (pinfunction "QD_11") (pintype "unspecified"))
      (node (ref "YIMAU2") (pin "6") (pinfunction "D_6") (pintype "unspecified"))
    )
    (net (code "83") (name "VCC") (class "Default")
      (node (ref "H1") (pin "1") (pinfunction "1_1") (pintype "input"))
      (node (ref "SEG1") (pin "3") (pinfunction "V1_3") (pintype "unspecified"))
      (node (ref "SEG1") (pin "8") (pinfunction "V2_8") (pintype "unspecified"))
      (node (ref "SEG2") (pin "3") (pinfunction "V1_3") (pintype "unspecified"))
      (node (ref "SEG2") (pin "8") (pinfunction "V2_8") (pintype "unspecified"))
      (node (ref "SEG3") (pin "3") (pinfunction "V1_3") (pintype "unspecified"))
      (node (ref "SEG3") (pin "8") (pinfunction "V2_8") (pintype "unspecified"))
      (node (ref "SEG4") (pin "3") (pinfunction "V1_3") (pintype "unspecified"))
      (node (ref "SEG4") (pin "8") (pinfunction "V2_8") (pintype "unspecified"))
      (node (ref "U1") (pin "10") (pinfunction "ENT_10") (pintype "unspecified"))
      (node (ref "U1") (pin "16") (pinfunction "VCC_16") (pintype "unspecified"))
      (node (ref "U1") (pin "7") (pinfunction "ENP_7") (pintype "unspecified"))
      (node (ref "U1") (pin "9") (pinfunction "LOAD_9") (pintype "unspecified"))
      (node (ref "U11") (pin "14") (pinfunction "VDD_14") (pintype "unspecified"))
      (node (ref "U12") (pin "16") (pinfunction "VDD_16") (pintype "unspecified"))
      (node (ref "U12") (pin "6") (pinfunction "(A=B)IN_6") (pintype "unspecified"))
      (node (ref "U13") (pin "16") (pinfunction "VDD_16") (pintype "unspecified"))
      (node (ref "U14") (pin "16") (pinfunction "VDD_16") (pintype "unspecified"))
      (node (ref "U14") (pin "6") (pinfunction "(A=B)IN_6") (pintype "unspecified"))
      (node (ref "U15") (pin "16") (pinfunction "VDD_16") (pintype "unspecified"))
      (node (ref "U2") (pin "10") (pinfunction "ENT_10") (pintype "unspecified"))
      (node (ref "U2") (pin "16") (pinfunction "VCC_16") (pintype "unspecified"))
      (node (ref "U2") (pin "7") (pinfunction "ENP_7") (pintype "unspecified"))
      (node (ref "U2") (pin "9") (pinfunction "LOAD_9") (pintype "unspecified"))
      (node (ref "U3") (pin "10") (pinfunction "ENT_10") (pintype "unspecified"))
      (node (ref "U3") (pin "16") (pinfunction "VCC_16") (pintype "unspecified"))
      (node (ref "U3") (pin "7") (pinfunction "ENP_7") (pintype "unspecified"))
      (node (ref "U3") (pin "9") (pinfunction "LOAD_9") (pintype "unspecified"))
      (node (ref "U4") (pin "1") (pinfunction "CLR_1") (pintype "unspecified"))
      (node (ref "U4") (pin "10") (pinfunction "ENT_10") (pintype "unspecified"))
      (node (ref "U4") (pin "16") (pinfunction "VCC_16") (pintype "unspecified"))
      (node (ref "U4") (pin "7") (pinfunction "ENP_7") (pintype "unspecified"))
      (node (ref "U4") (pin "9") (pinfunction "LOAD_9") (pintype "unspecified"))
      (node (ref "U5") (pin "14") (pinfunction "VCC_14") (pintype "unspecified"))
      (node (ref "U6") (pin "14") (pinfunction "VCC_14") (pintype "unspecified"))
      (node (ref "YIMAU1") (pin "16") (pinfunction "VCC_16") (pintype "passive"))
      (node (ref "YIMAU1") (pin "3") (pinfunction "LT_3") (pintype "unspecified"))
      (node (ref "YIMAU1") (pin "4") (pinfunction "BIRBO_4") (pintype "bidirectional"))
      (node (ref "YIMAU1") (pin "5") (pinfunction "RBI_5") (pintype "unspecified"))
      (node (ref "YIMAU2") (pin "16") (pinfunction "VCC_16") (pintype "passive"))
      (node (ref "YIMAU2") (pin "3") (pinfunction "LT_3") (pintype "unspecified"))
      (node (ref "YIMAU2") (pin "4") (pinfunction "BIRBO_4") (pintype "bidirectional"))
      (node (ref "YIMAU2") (pin "5") (pinfunction "RBI_5") (pintype "unspecified"))
      (node (ref "YIMAU3") (pin "16") (pinfunction "VCC_16") (pintype "passive"))
      (node (ref "YIMAU3") (pin "3") (pinfunction "LT_3") (pintype "unspecified"))
      (node (ref "YIMAU3") (pin "4") (pinfunction "BIRBO_4") (pintype "bidirectional"))
      (node (ref "YIMAU3") (pin "5") (pinfunction "RBI_5") (pintype "unspecified"))
      (node (ref "YIMAU4") (pin "16") (pinfunction "VCC_16") (pintype "passive"))
      (node (ref "YIMAU4") (pin "3") (pinfunction "LT_3") (pintype "unspecified"))
      (node (ref "YIMAU4") (pin "4") (pinfunction "BIRBO_4") (pintype "bidirectional"))
      (node (ref "YIMAU4") (pin "5") (pinfunction "RBI_5") (pintype "unspecified"))
    )
    (net (code "84") (name "unconnected-(SEG1-DP-Pad5)") (class "Default")
      (node (ref "SEG1") (pin "5") (pinfunction "DP_5") (pintype "unspecified"))
    )
    (net (code "85") (name "unconnected-(SEG2-DP-Pad5)") (class "Default")
      (node (ref "SEG2") (pin "5") (pinfunction "DP_5") (pintype "unspecified"))
    )
    (net (code "86") (name "unconnected-(SEG3-DP-Pad5)") (class "Default")
      (node (ref "SEG3") (pin "5") (pinfunction "DP_5") (pintype "unspecified"))
    )
    (net (code "87") (name "unconnected-(SEG4-DP-Pad5)") (class "Default")
      (node (ref "SEG4") (pin "5") (pinfunction "DP_5") (pintype "unspecified"))
    )
    (net (code "88") (name "unconnected-(U1-A-Pad3)") (class "Default")
      (node (ref "U1") (pin "3") (pinfunction "A_3") (pintype "unspecified"))
    )
    (net (code "89") (name "unconnected-(U1-B-Pad4)") (class "Default")
      (node (ref "U1") (pin "4") (pinfunction "B_4") (pintype "unspecified"))
    )
    (net (code "90") (name "unconnected-(U1-C-Pad5)") (class "Default")
      (node (ref "U1") (pin "5") (pinfunction "C_5") (pintype "unspecified"))
    )
    (net (code "91") (name "unconnected-(U1-D-Pad6)") (class "Default")
      (node (ref "U1") (pin "6") (pinfunction "D_6") (pintype "unspecified"))
    )
    (net (code "92") (name "unconnected-(U1-RCO-Pad15)") (class "Default")
      (node (ref "U1") (pin "15") (pinfunction "RCO_15") (pintype "unspecified"))
    )
    (net (code "93") (name "unconnected-(U2-A-Pad3)") (class "Default")
      (node (ref "U2") (pin "3") (pinfunction "A_3") (pintype "unspecified"))
    )
    (net (code "94") (name "unconnected-(U2-B-Pad4)") (class "Default")
      (node (ref "U2") (pin "4") (pinfunction "B_4") (pintype "unspecified"))
    )
    (net (code "95") (name "unconnected-(U2-C-Pad5)") (class "Default")
      (node (ref "U2") (pin "5") (pinfunction "C_5") (pintype "unspecified"))
    )
    (net (code "96") (name "unconnected-(U2-D-Pad6)") (class "Default")
      (node (ref "U2") (pin "6") (pinfunction "D_6") (pintype "unspecified"))
    )
    (net (code "97") (name "unconnected-(U3-A-Pad3)") (class "Default")
      (node (ref "U3") (pin "3") (pinfunction "A_3") (pintype "unspecified"))
    )
    (net (code "98") (name "unconnected-(U3-B-Pad4)") (class "Default")
      (node (ref "U3") (pin "4") (pinfunction "B_4") (pintype "unspecified"))
    )
    (net (code "99") (name "unconnected-(U3-C-Pad5)") (class "Default")
      (node (ref "U3") (pin "5") (pinfunction "C_5") (pintype "unspecified"))
    )
    (net (code "100") (name "unconnected-(U3-D-Pad6)") (class "Default")
      (node (ref "U3") (pin "6") (pinfunction "D_6") (pintype "unspecified"))
    )
    (net (code "101") (name "unconnected-(U3-RCO-Pad15)") (class "Default")
      (node (ref "U3") (pin "15") (pinfunction "RCO_15") (pintype "unspecified"))
    )
    (net (code "102") (name "unconnected-(U4-A-Pad3)") (class "Default")
      (node (ref "U4") (pin "3") (pinfunction "A_3") (pintype "unspecified"))
    )
    (net (code "103") (name "unconnected-(U4-B-Pad4)") (class "Default")
      (node (ref "U4") (pin "4") (pinfunction "B_4") (pintype "unspecified"))
    )
    (net (code "104") (name "unconnected-(U4-C-Pad5)") (class "Default")
      (node (ref "U4") (pin "5") (pinfunction "C_5") (pintype "unspecified"))
    )
    (net (code "105") (name "unconnected-(U4-D-Pad6)") (class "Default")
      (node (ref "U4") (pin "6") (pinfunction "D_6") (pintype "unspecified"))
    )
    (net (code "106") (name "unconnected-(U5-2A-Pad4)") (class "Default")
      (node (ref "U5") (pin "4") (pinfunction "2A_4") (pintype "unspecified"))
    )
    (net (code "107") (name "unconnected-(U5-2B-Pad5)") (class "Default")
      (node (ref "U5") (pin "5") (pinfunction "2B_5") (pintype "unspecified"))
    )
    (net (code "108") (name "unconnected-(U5-2Y-Pad6)") (class "Default")
      (node (ref "U5") (pin "6") (pinfunction "2Y_6") (pintype "unspecified"))
    )
    (net (code "109") (name "unconnected-(U5-3A-Pad9)") (class "Default")
      (node (ref "U5") (pin "9") (pinfunction "3A_9") (pintype "unspecified"))
    )
    (net (code "110") (name "unconnected-(U5-3B-Pad10)") (class "Default")
      (node (ref "U5") (pin "10") (pinfunction "3B_10") (pintype "unspecified"))
    )
    (net (code "111") (name "unconnected-(U5-3Y-Pad8)") (class "Default")
      (node (ref "U5") (pin "8") (pinfunction "3Y_8") (pintype "unspecified"))
    )
    (net (code "112") (name "unconnected-(U6-2A-Pad3)") (class "Default")
      (node (ref "U6") (pin "3") (pinfunction "2A_3") (pintype "unspecified"))
    )
    (net (code "113") (name "unconnected-(U6-2Y-Pad4)") (class "Default")
      (node (ref "U6") (pin "4") (pinfunction "2Y_4") (pintype "unspecified"))
    )
    (net (code "114") (name "unconnected-(U6-4A-Pad9)") (class "Default")
      (node (ref "U6") (pin "9") (pinfunction "4A_9") (pintype "unspecified"))
    )
    (net (code "115") (name "unconnected-(U6-4Y-Pad8)") (class "Default")
      (node (ref "U6") (pin "8") (pinfunction "4Y_8") (pintype "unspecified"))
    )
    (net (code "116") (name "unconnected-(U6-5A-Pad11)") (class "Default")
      (node (ref "U6") (pin "11") (pinfunction "5A_11") (pintype "unspecified"))
    )
    (net (code "117") (name "unconnected-(U6-5Y-Pad10)") (class "Default")
      (node (ref "U6") (pin "10") (pinfunction "5Y_10") (pintype "unspecified"))
    )
    (net (code "118") (name "unconnected-(U6-6A-Pad13)") (class "Default")
      (node (ref "U6") (pin "13") (pinfunction "6A_13") (pintype "unspecified"))
    )
    (net (code "119") (name "unconnected-(U6-6Y-Pad12)") (class "Default")
      (node (ref "U6") (pin "12") (pinfunction "6Y_12") (pintype "unspecified"))
    )
    (net (code "120") (name "unconnected-(U11-A-Pad1)") (class "Default")
      (node (ref "U11") (pin "1") (pinfunction "A_1") (pintype "unspecified"))
    )
    (net (code "121") (name "unconnected-(U11-B-Pad2)") (class "Default")
      (node (ref "U11") (pin "2") (pinfunction "B_2") (pintype "unspecified"))
    )
    (net (code "122") (name "unconnected-(U11-C-Pad8)") (class "Default")
      (node (ref "U11") (pin "8") (pinfunction "C_8") (pintype "unspecified"))
    )
    (net (code "123") (name "unconnected-(U11-G-Pad13)") (class "Default")
      (node (ref "U11") (pin "13") (pinfunction "G_13") (pintype "unspecified"))
    )
    (net (code "124") (name "unconnected-(U11-H-Pad12)") (class "Default")
      (node (ref "U11") (pin "12") (pinfunction "H_12") (pintype "unspecified"))
    )
    (net (code "125") (name "unconnected-(U11-I-Pad11)") (class "Default")
      (node (ref "U11") (pin "11") (pinfunction "I_11") (pintype "unspecified"))
    )
    (net (code "126") (name "unconnected-(U11-J-Pad9)") (class "Default")
      (node (ref "U11") (pin "9") (pinfunction "J_9") (pintype "unspecified"))
    )
    (net (code "127") (name "unconnected-(U11-L-Pad10)") (class "Default")
      (node (ref "U11") (pin "10") (pinfunction "L_10") (pintype "unspecified"))
    )
    (net (code "128") (name "unconnected-(U13-(A&gt;B)OUT-Pad13)") (class "Default")
      (node (ref "U13") (pin "13") (pinfunction "(A&gt;B)OUT_13") (pintype "unspecified"))
    )
    (net (code "129") (name "unconnected-(U13-(A&lt;B)OUT-Pad12)") (class "Default")
      (node (ref "U13") (pin "12") (pinfunction "(A&lt;B)OUT_12") (pintype "unspecified"))
    )
    (net (code "130") (name "unconnected-(U15-(A&gt;B)OUT-Pad13)") (class "Default")
      (node (ref "U15") (pin "13") (pinfunction "(A&gt;B)OUT_13") (pintype "unspecified"))
    )
    (net (code "131") (name "unconnected-(U15-(A&lt;B)OUT-Pad12)") (class "Default")
      (node (ref "U15") (pin "12") (pinfunction "(A&lt;B)OUT_12") (pintype "unspecified"))
    )
  )
)
